# PCB_Design.net
KiCad netlist of a schematic drawn in EAGLE
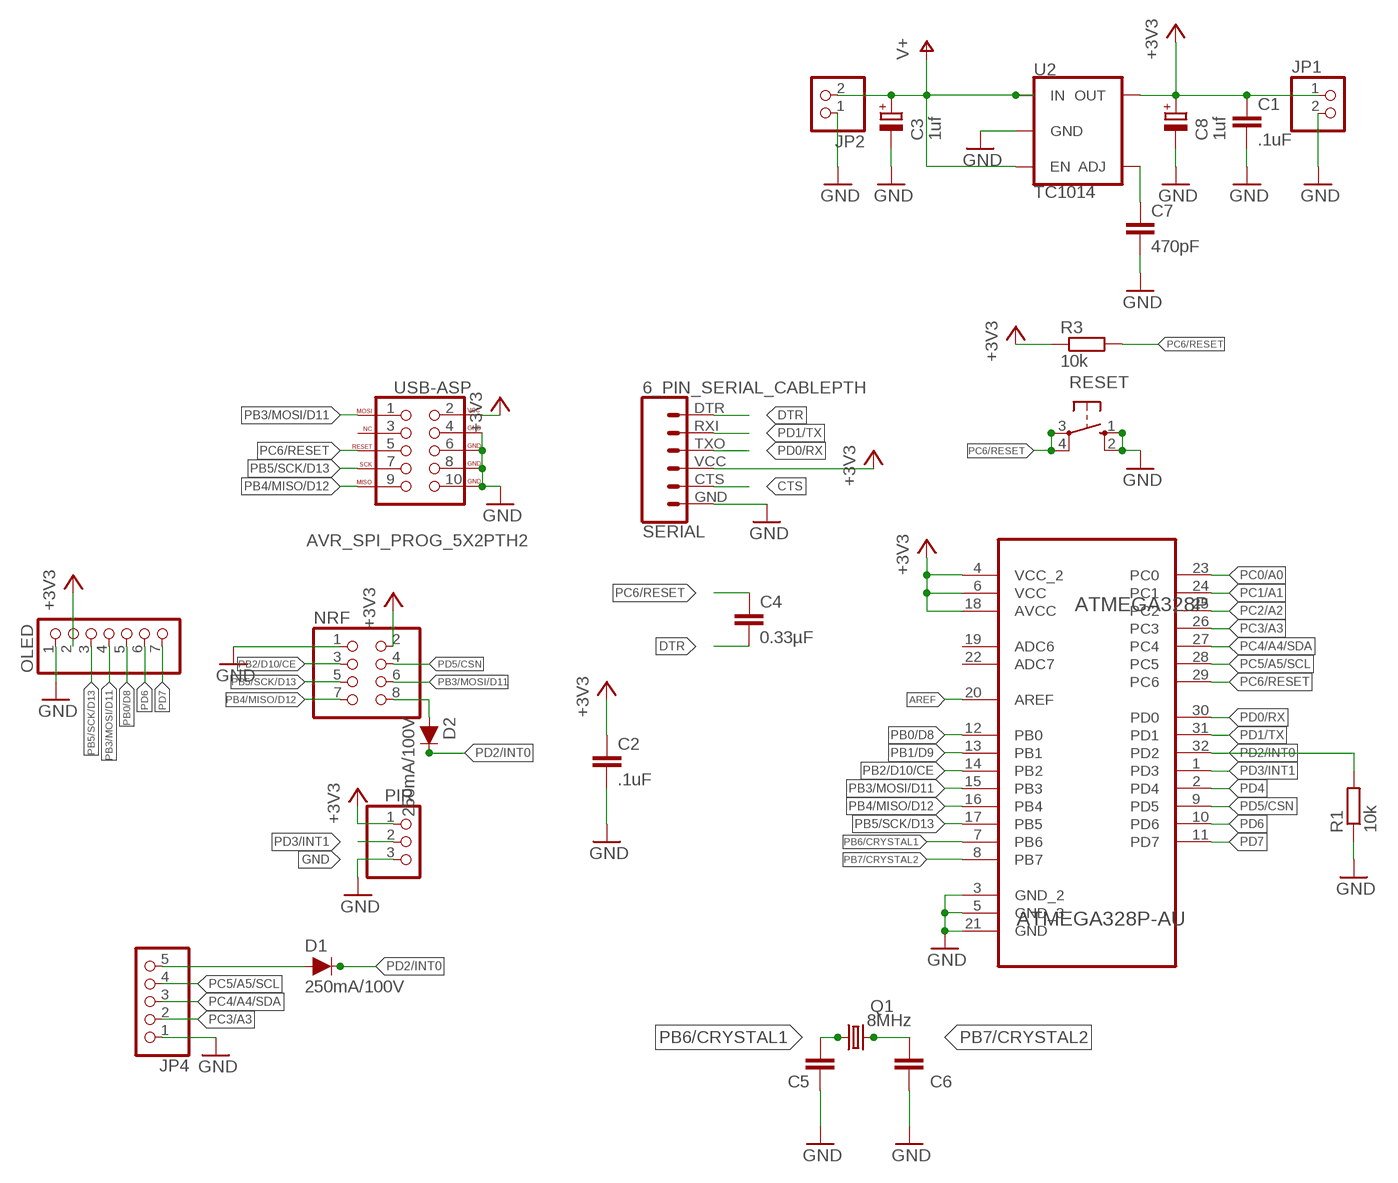
[diagram p0: schematic, sheet 1]

(export (version "E")
  (design (tool "Eeschema 10.0.6"))
  (components
    (comp (ref "ATMEGA328P")
      (value "ATMEGA328P-AU")
      (footprint "eagle-import:QFP80P900X900X120-32N")
      (fields (field (name "MF") "MICROCHIP"))
      (libsource (lib "eagle-import") (part "ATMEGA328P-AU"))
    )
    (comp (ref "C1")
      (value ".1uF")
      (footprint "eagle-import:C0805K")
      (libsource (lib "eagle-import") (part "C-EUC0805K"))
    )
    (comp (ref "C2")
      (value ".1uF")
      (footprint "eagle-import:C0805K")
      (libsource (lib "eagle-import") (part "C-EUC0805K"))
    )
    (comp (ref "C3")
      (value "1uf")
      (footprint "eagle-import:E2,5-5")
      (libsource (lib "eagle-import") (part "CPOL-EUE2.5-5"))
    )
    (comp (ref "C4")
      (value "0.33µF")
      (footprint "eagle-import:C0805K")
      (libsource (lib "eagle-import") (part "C-EUC0805K"))
    )
    (comp (ref "C5")
      (value "22pF")
      (footprint "eagle-import:C0805K")
      (libsource (lib "eagle-import") (part "C-EUC0805K"))
    )
    (comp (ref "C6")
      (value "22pF")
      (footprint "eagle-import:C0805K")
      (libsource (lib "eagle-import") (part "C-EUC0805K"))
    )
    (comp (ref "C7")
      (value "470pF")
      (footprint "eagle-import:C0805K")
      (libsource (lib "eagle-import") (part "C-EUC0805K"))
    )
    (comp (ref "C8")
      (value "1uf")
      (footprint "eagle-import:E2,5-5")
      (libsource (lib "eagle-import") (part "CPOL-EUE2.5-5"))
    )
    (comp (ref "D1")
      (value "250mA/100V")
      (footprint "eagle-import:SOD-323")
      (fields (field (name "MF") "SCHMERSAL") (field (name "MPN") "BNS33-11ZG-3M"))
      (libsource (lib "eagle-import") (part "DIODE-BAS16J"))
    )
    (comp (ref "D2")
      (value "250mA/100V")
      (footprint "eagle-import:SOD-323")
      (fields (field (name "MF") "SCHMERSAL") (field (name "MPN") "BNS33-11ZG-3M"))
      (libsource (lib "eagle-import") (part "DIODE-BAS16J"))
    )
    (comp (ref "JP1")
      (value "PINHD-1X2")
      (footprint "eagle-import:1X02")
      (libsource (lib "eagle-import") (part "PINHD-1X2"))
    )
    (comp (ref "JP2")
      (value "PINHD-1X2")
      (footprint "eagle-import:1X02")
      (libsource (lib "eagle-import") (part "PINHD-1X2"))
    )
    (comp (ref "JP4")
      (value "PINHD-1X5")
      (footprint "eagle-import:1X05")
      (libsource (lib "eagle-import") (part "PINHD-1X5"))
    )
    (comp (ref "NRF")
      (value "PINHD-2X4")
      (footprint "eagle-import:2X04")
      (libsource (lib "eagle-import") (part "PINHD-2X4"))
    )
    (comp (ref "OLED")
      (value "PINHD-1X7")
      (footprint "eagle-import:1X07")
      (libsource (lib "eagle-import") (part "PINHD-1X7"))
    )
    (comp (ref "PIR")
      (value "PINHD-1X3")
      (footprint "eagle-import:1X03")
      (libsource (lib "eagle-import") (part "PINHD-1X3"))
    )
    (comp (ref "Q1")
      (value "8MHz")
      (footprint "eagle-import:HC49U70")
      (libsource (lib "eagle-import") (part "CRYSTALHC49U70"))
    )
    (comp (ref "R1")
      (value "10k")
      (footprint "eagle-import:M0805")
      (libsource (lib "eagle-import") (part "R-EU_M0805"))
    )
    (comp (ref "R3")
      (value "10k")
      (footprint "eagle-import:M0805")
      (libsource (lib "eagle-import") (part "R-EU_M0805"))
    )
    (comp (ref "RESET")
      (value "10-XX")
      (footprint "eagle-import:B3F-10XX")
      (fields (field (name "MPN") "B3F-1000") (field (name "MF") "OMRON ELECTRONIC COMPONENTS"))
      (libsource (lib "eagle-import") (part "10-XX"))
    )
    (comp (ref "SERIAL")
      (value "6_PIN_SERIAL_CABLEPTH")
      (footprint "eagle-import:FTDI_BASIC")
      (libsource (lib "eagle-import") (part "6_PIN_SERIAL_CABLEPTH"))
    )
    (comp (ref "U2")
      (value "TC1014")
      (footprint "eagle-import:SOT23-5")
      (libsource (lib "eagle-import") (part "AP2202-ADJ"))
    )
    (comp (ref "USB-ASP")
      (value "AVR_SPI_PROG_5X2PTH2")
      (footprint "eagle-import:2X5-SHROUDED")
      (libsource (lib "eagle-import") (part "AVR_SPI_PROG_5X2PTH2"))
    )
  )
  (nets
    (net (code "1") (name "+3V3") (class "Default")
      (node (ref "ATMEGA328P") (pin "18") (pinfunction "AVCC_18") (pintype "power_in"))
      (node (ref "ATMEGA328P") (pin "4") (pinfunction "VCC_2_4") (pintype "power_in"))
      (node (ref "ATMEGA328P") (pin "6") (pinfunction "VCC_6") (pintype "power_in"))
      (node (ref "C1") (pin "1") (pinfunction "1_1") (pintype "passive"))
      (node (ref "C2") (pin "1") (pinfunction "1_1") (pintype "passive"))
      (node (ref "C8") (pin "+") (pinfunction "+_+") (pintype "passive"))
      (node (ref "JP1") (pin "1") (pinfunction "1_1") (pintype "passive"))
      (node (ref "NRF") (pin "2") (pinfunction "2_2") (pintype "passive"))
      (node (ref "OLED") (pin "2") (pinfunction "2_2") (pintype "passive"))
      (node (ref "PIR") (pin "1") (pinfunction "1_1") (pintype "passive"))
      (node (ref "R3") (pin "1") (pinfunction "1_1") (pintype "passive"))
      (node (ref "SERIAL") (pin "VCC") (pinfunction "4_VCC") (pintype "passive"))
      (node (ref "U2") (pin "5") (pinfunction "OUT_5") (pintype "passive"))
      (node (ref "USB-ASP") (pin "2") (pinfunction "VCC_2") (pintype "power_in"))
    )
    (net (code "2") (name "AREF") (class "Default")
      (node (ref "ATMEGA328P") (pin "20") (pinfunction "AREF_20") (pintype "input"))
    )
    (net (code "3") (name "CTS") (class "Default")
      (node (ref "SERIAL") (pin "CTS") (pinfunction "5_CTS") (pintype "passive"))
    )
    (net (code "4") (name "DTR") (class "Default")
      (node (ref "C4") (pin "2") (pinfunction "2_2") (pintype "passive"))
      (node (ref "SERIAL") (pin "DTR") (pinfunction "1_DTR") (pintype "passive"))
    )
    (net (code "5") (name "GND") (class "Default")
      (node (ref "ATMEGA328P") (pin "21") (pinfunction "GND_21") (pintype "passive"))
      (node (ref "ATMEGA328P") (pin "3") (pinfunction "GND_2_3") (pintype "passive"))
      (node (ref "ATMEGA328P") (pin "5") (pinfunction "GND_3_5") (pintype "passive"))
      (node (ref "C1") (pin "2") (pinfunction "2_2") (pintype "passive"))
      (node (ref "C2") (pin "2") (pinfunction "2_2") (pintype "passive"))
      (node (ref "C3") (pin "-") (pinfunction "-_-") (pintype "passive"))
      (node (ref "C5") (pin "1") (pinfunction "1_1") (pintype "passive"))
      (node (ref "C6") (pin "1") (pinfunction "1_1") (pintype "passive"))
      (node (ref "C7") (pin "2") (pinfunction "2_2") (pintype "passive"))
      (node (ref "C8") (pin "-") (pinfunction "-_-") (pintype "passive"))
      (node (ref "JP1") (pin "2") (pinfunction "2_2") (pintype "passive"))
      (node (ref "JP2") (pin "1") (pinfunction "1_1") (pintype "passive"))
      (node (ref "JP4") (pin "1") (pinfunction "1_1") (pintype "passive"))
      (node (ref "NRF") (pin "1") (pinfunction "1_1") (pintype "passive"))
      (node (ref "OLED") (pin "1") (pinfunction "1_1") (pintype "passive"))
      (node (ref "PIR") (pin "3") (pinfunction "3_3") (pintype "passive"))
      (node (ref "R1") (pin "1") (pinfunction "1_1") (pintype "passive"))
      (node (ref "RESET") (pin "1") (pinfunction "S_1") (pintype "passive"))
      (node (ref "RESET") (pin "2") (pinfunction "S1_2") (pintype "passive"))
      (node (ref "SERIAL") (pin "GND") (pinfunction "6_GND") (pintype "passive"))
      (node (ref "U2") (pin "2") (pinfunction "GND_2") (pintype "input"))
      (node (ref "USB-ASP") (pin "10") (pinfunction "GND_10") (pintype "power_in"))
      (node (ref "USB-ASP") (pin "4") (pinfunction "GND_4") (pintype "power_in"))
      (node (ref "USB-ASP") (pin "6") (pinfunction "GND_6") (pintype "power_in"))
      (node (ref "USB-ASP") (pin "8") (pinfunction "GND_8") (pintype "power_in"))
    )
    (net (code "6") (name "Net-(D1-PadA)") (class "Default")
      (node (ref "D1") (pin "A") (pinfunction "A_A") (pintype "passive"))
      (node (ref "JP4") (pin "5") (pinfunction "5_5") (pintype "passive"))
    )
    (net (code "7") (name "Net-(D2-PadA)") (class "Default")
      (node (ref "D2") (pin "A") (pinfunction "A_A") (pintype "passive"))
      (node (ref "NRF") (pin "8") (pinfunction "8_8") (pintype "passive"))
    )
    (net (code "8") (name "Net-(U2-ADJ)") (class "Default")
      (node (ref "C7") (pin "1") (pinfunction "1_1") (pintype "passive"))
      (node (ref "U2") (pin "4") (pinfunction "ADJ_4") (pintype "input"))
    )
    (net (code "9") (name "PB0{slash}D8") (class "Default")
      (node (ref "ATMEGA328P") (pin "12") (pinfunction "PB0_12") (pintype "bidirectional"))
      (node (ref "OLED") (pin "5") (pinfunction "5_5") (pintype "passive"))
    )
    (net (code "10") (name "PB1{slash}D9") (class "Default")
      (node (ref "ATMEGA328P") (pin "13") (pinfunction "PB1_13") (pintype "bidirectional"))
    )
    (net (code "11") (name "PB2{slash}D10{slash}CE") (class "Default")
      (node (ref "ATMEGA328P") (pin "14") (pinfunction "PB2_14") (pintype "bidirectional"))
      (node (ref "NRF") (pin "3") (pinfunction "3_3") (pintype "passive"))
    )
    (net (code "12") (name "PB3{slash}MOSI{slash}D11") (class "Default")
      (node (ref "ATMEGA328P") (pin "15") (pinfunction "PB3_15") (pintype "bidirectional"))
      (node (ref "NRF") (pin "6") (pinfunction "6_6") (pintype "passive"))
      (node (ref "OLED") (pin "4") (pinfunction "4_4") (pintype "passive"))
      (node (ref "USB-ASP") (pin "1") (pinfunction "MOSI_1") (pintype "passive"))
    )
    (net (code "13") (name "PB4{slash}MISO{slash}D12") (class "Default")
      (node (ref "ATMEGA328P") (pin "16") (pinfunction "PB4_16") (pintype "bidirectional"))
      (node (ref "NRF") (pin "7") (pinfunction "7_7") (pintype "passive"))
      (node (ref "USB-ASP") (pin "9") (pinfunction "MISO_9") (pintype "passive"))
    )
    (net (code "14") (name "PB5{slash}SCK{slash}D13") (class "Default")
      (node (ref "ATMEGA328P") (pin "17") (pinfunction "PB5_17") (pintype "bidirectional"))
      (node (ref "NRF") (pin "5") (pinfunction "5_5") (pintype "passive"))
      (node (ref "OLED") (pin "3") (pinfunction "3_3") (pintype "passive"))
      (node (ref "USB-ASP") (pin "7") (pinfunction "SCK_7") (pintype "passive"))
    )
    (net (code "15") (name "PB6{slash}CRYSTAL1") (class "Default")
      (node (ref "ATMEGA328P") (pin "7") (pinfunction "PB6_7") (pintype "bidirectional"))
      (node (ref "C5") (pin "2") (pinfunction "2_2") (pintype "passive"))
      (node (ref "Q1") (pin "1") (pinfunction "1_1") (pintype "passive"))
    )
    (net (code "16") (name "PB7{slash}CRYSTAL2") (class "Default")
      (node (ref "ATMEGA328P") (pin "8") (pinfunction "PB7_8") (pintype "bidirectional"))
      (node (ref "C6") (pin "2") (pinfunction "2_2") (pintype "passive"))
      (node (ref "Q1") (pin "2") (pinfunction "2_2") (pintype "passive"))
    )
    (net (code "17") (name "PC0{slash}A0") (class "Default")
      (node (ref "ATMEGA328P") (pin "23") (pinfunction "PC0_23") (pintype "bidirectional"))
    )
    (net (code "18") (name "PC1{slash}A1") (class "Default")
      (node (ref "ATMEGA328P") (pin "24") (pinfunction "PC1_24") (pintype "bidirectional"))
    )
    (net (code "19") (name "PC2{slash}A2") (class "Default")
      (node (ref "ATMEGA328P") (pin "25") (pinfunction "PC2_25") (pintype "bidirectional"))
    )
    (net (code "20") (name "PC3{slash}A3") (class "Default")
      (node (ref "ATMEGA328P") (pin "26") (pinfunction "PC3_26") (pintype "bidirectional"))
      (node (ref "JP4") (pin "2") (pinfunction "2_2") (pintype "passive"))
    )
    (net (code "21") (name "PC4{slash}A4{slash}SDA") (class "Default")
      (node (ref "ATMEGA328P") (pin "27") (pinfunction "PC4_27") (pintype "bidirectional"))
      (node (ref "JP4") (pin "3") (pinfunction "3_3") (pintype "passive"))
    )
    (net (code "22") (name "PC5{slash}A5{slash}SCL") (class "Default")
      (node (ref "ATMEGA328P") (pin "28") (pinfunction "PC5_28") (pintype "bidirectional"))
      (node (ref "JP4") (pin "4") (pinfunction "4_4") (pintype "passive"))
    )
    (net (code "23") (name "PC6{slash}RESET") (class "Default")
      (node (ref "ATMEGA328P") (pin "29") (pinfunction "PC6_29") (pintype "bidirectional"))
      (node (ref "C4") (pin "1") (pinfunction "1_1") (pintype "passive"))
      (node (ref "R3") (pin "2") (pinfunction "2_2") (pintype "passive"))
      (node (ref "RESET") (pin "3") (pinfunction "P_3") (pintype "passive"))
      (node (ref "RESET") (pin "4") (pinfunction "P1_4") (pintype "passive"))
      (node (ref "USB-ASP") (pin "5") (pinfunction "RESET_5") (pintype "passive"))
    )
    (net (code "24") (name "PD0{slash}RX") (class "Default")
      (node (ref "ATMEGA328P") (pin "30") (pinfunction "PD0_30") (pintype "bidirectional"))
      (node (ref "SERIAL") (pin "TXO") (pinfunction "3_TXO") (pintype "passive"))
    )
    (net (code "25") (name "PD1{slash}TX") (class "Default")
      (node (ref "ATMEGA328P") (pin "31") (pinfunction "PD1_31") (pintype "bidirectional"))
      (node (ref "SERIAL") (pin "RXI") (pinfunction "2_RXI") (pintype "passive"))
    )
    (net (code "26") (name "PD2{slash}INT0") (class "Default")
      (node (ref "ATMEGA328P") (pin "32") (pinfunction "PD2_32") (pintype "bidirectional"))
      (node (ref "D1") (pin "C") (pinfunction "C_C") (pintype "passive"))
      (node (ref "D2") (pin "C") (pinfunction "C_C") (pintype "passive"))
      (node (ref "R1") (pin "2") (pinfunction "2_2") (pintype "passive"))
    )
    (net (code "27") (name "PD3{slash}INT1") (class "Default")
      (node (ref "ATMEGA328P") (pin "1") (pinfunction "PD3_1") (pintype "bidirectional"))
      (node (ref "PIR") (pin "2") (pinfunction "2_2") (pintype "passive"))
    )
    (net (code "28") (name "PD4") (class "Default")
      (node (ref "ATMEGA328P") (pin "2") (pinfunction "PD4_2") (pintype "bidirectional"))
    )
    (net (code "29") (name "PD5{slash}CSN") (class "Default")
      (node (ref "ATMEGA328P") (pin "9") (pinfunction "PD5_9") (pintype "bidirectional"))
      (node (ref "NRF") (pin "4") (pinfunction "4_4") (pintype "passive"))
    )
    (net (code "30") (name "PD6") (class "Default")
      (node (ref "ATMEGA328P") (pin "10") (pinfunction "PD6_10") (pintype "bidirectional"))
      (node (ref "OLED") (pin "6") (pinfunction "6_6") (pintype "passive"))
    )
    (net (code "31") (name "PD7") (class "Default")
      (node (ref "ATMEGA328P") (pin "11") (pinfunction "PD7_11") (pintype "bidirectional"))
      (node (ref "OLED") (pin "7") (pinfunction "7_7") (pintype "passive"))
    )
    (net (code "32") (name "V+") (class "Default")
      (node (ref "C3") (pin "+") (pinfunction "+_+") (pintype "passive"))
      (node (ref "JP2") (pin "2") (pinfunction "2_2") (pintype "passive"))
      (node (ref "U2") (pin "1") (pinfunction "IN_1") (pintype "input"))
      (node (ref "U2") (pin "3") (pinfunction "EN_3") (pintype "input"))
    )
    (net (code "33") (name "unconnected-(ATMEGA328P-ADC6-Pad19)") (class "Default")
      (node (ref "ATMEGA328P") (pin "19") (pinfunction "ADC6_19") (pintype "input"))
    )
    (net (code "34") (name "unconnected-(ATMEGA328P-ADC7-Pad22)") (class "Default")
      (node (ref "ATMEGA328P") (pin "22") (pinfunction "ADC7_22") (pintype "input"))
    )
    (net (code "35") (name "unconnected-(USB-ASP-NC-Pad3)") (class "Default")
      (node (ref "USB-ASP") (pin "3") (pinfunction "NC_3") (pintype "no_connect"))
    )
  )
)
